# GNSS-receiver.net
KiCad netlist of a schematic drawn in Altium Designer
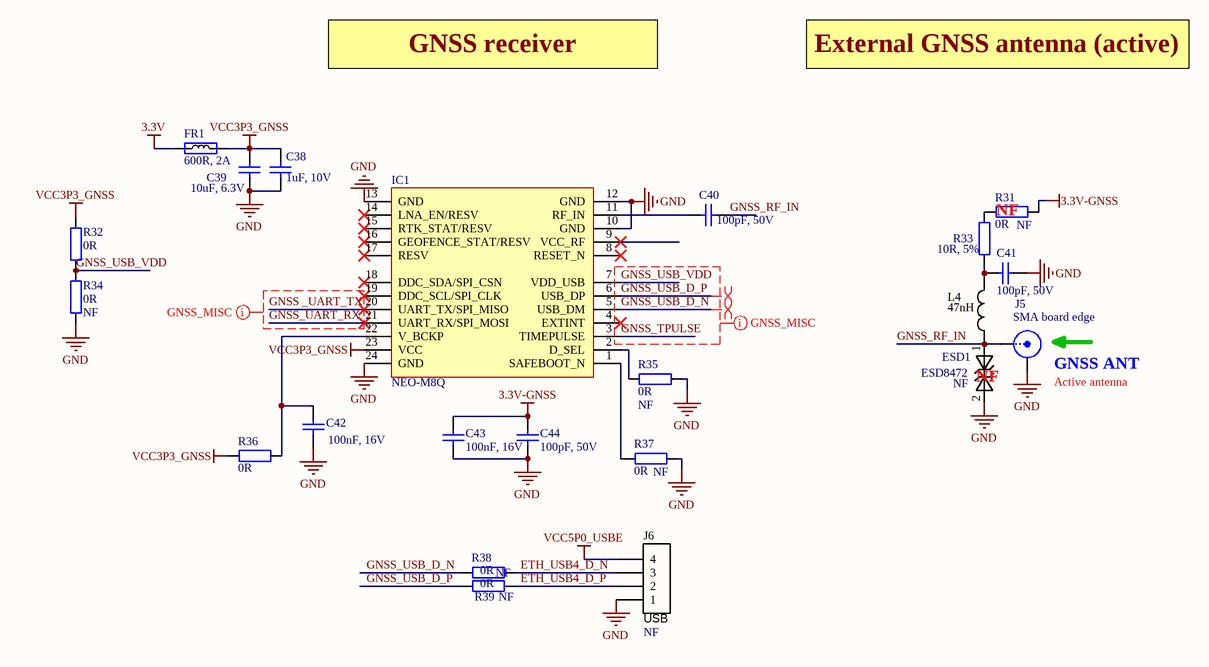
[diagram p0: GNSS-receiver.SchDoc]

(export (version "E")
  (design (tool "Eeschema 10.0.6"))
  (components
    (comp (ref "C38")
      (value "1uF, 10V")
      (footprint "CAP0402")
      (description "CAP CER 1UF 10V X5R 0402")
      (fields (field (name "MANUFACTURER") "Yageo") (field (name "TOLERANCE") "±20%"))
      (libsource (lib "LimeMicroAltiumLib_schLib") (part "Cap_0402"))
    )
    (comp (ref "C39")
      (value "10uF, 6.3V")
      (footprint "CAP0603")
      (fields (field (name "TOLERANCE") "±20%") (field (name "MANUFACTURER") "Yageo"))
      (libsource (lib "LimeFPGAboard_schLib") (part "Cap_0603"))
    )
    (comp (ref "C40")
      (value "100pF, 50V")
      (footprint "CAP0402")
      (fields (field (name "TOLERANCE") "±5%") (field (name "MANUFACTURER") "Yageo"))
      (libsource (lib "LimeMicroAltiumLib_schLib") (part "Cap_0402"))
    )
    (comp (ref "C41")
      (value "100pF, 50V")
      (footprint "CAP0402")
      (fields (field (name "TOLERANCE") "±5%") (field (name "MANUFACTURER") "Yageo"))
      (libsource (lib "LimeMicroAltiumLib_schLib") (part "Cap_0402"))
    )
    (comp (ref "C42")
      (value "100nF, 16V")
      (footprint "CAP0402")
      (fields
        (field (name "TOLERANCE") "10 %")
        (field (name "MANUFACTURER") "Murata Electronics")
        (field (name "MANUFACTURER PART NUMBER") "GRM155R71C104KA88D")
      )
      (libsource (lib "LimeFPGAboard_schLib") (part "Cap_0603"))
    )
    (comp (ref "C43")
      (value "100nF, 16V")
      (footprint "CAP0402")
      (fields
        (field (name "MANUFACTURER") "Murata Electronics")
        (field (name "TOLERANCE") "10 %")
        (field (name "MANUFACTURER PART NUMBER") "GRM155R71C104KA88D")
      )
      (libsource (lib "LimeMicroAltiumLib_schLib") (part "Cap_0402"))
    )
    (comp (ref "C44")
      (value "100pF, 50V")
      (footprint "CAP0402")
      (fields (field (name "TOLERANCE") "±5%") (field (name "MANUFACTURER") "Yageo"))
      (libsource (lib "LimeMicroAltiumLib_schLib") (part "Cap_0402"))
    )
    (comp (ref "ESD1")
      (value "ESD8472")
      (footprint "ESD8472_X3DFN2")
      (fields (field (name "MANUFACTURER") "ON Semiconductor") (field (name "ASSEMBLY INFO") "NF"))
      (libsource (lib "LimeMicroAltiumLib_schLib") (part "ESD8472"))
    )
    (comp (ref "FR1")
      (value "600R, 2A")
      (footprint "RES0805")
      (fields (field (name "MANUFACTURER") "TDK Corporation"))
      (libsource (lib "LimeFPGAboard_schLib") (part "Ferrite"))
    )
    (comp (ref "IC1")
      (value "NEO-M8Q")
      (footprint "NEO-7M/8M")
      (description "GNSS engine for GPS/QZSS, GLONASS")
      (fields (field (name "MANUFACTURER") "u-blox") (field (name "MANUFACTURER PART NUMBER") "NEO-M8Q-0"))
      (libsource (lib "LimeMicroAltiumLib_schLib") (part "NEO-M8P_M8M"))
    )
    (comp (ref "J5")
      (value "SMA board edge")
      (footprint "SMA_connector_board_edge_SM")
      (description "CONN SMA JACK STR 50OHM EDGE MNT")
      (fields (field (name "MANUFACTURER") "RF Solutions"))
      (libsource (lib "LimeMicroAltiumLib_schLib") (part "RF_IF_connector"))
    )
    (comp (ref "J6")
      (value "USB")
      (footprint "HEADER4X1_TH")
      (description "Header, 4-pin")
      (fields (field (name "ASSEMBLY INFO") "NF") (field (name "MANUFACTURER") "Wurth Electronics Inc."))
      (libsource (lib "LimeMicroAltiumLib_schLib") (part "Header4P"))
    )
    (comp (ref "L4")
      (value "47nH")
      (footprint "RES0402")
      (fields
        (field (name "MANUFACTURER") "COILCRAFT")
        (field (name "MANUFACTURER PART NUMBER") "0402HP-47NXJLU")
      )
      (libsource (lib "LimeMicroAltiumLib_schLib") (part "Inductor_0603"))
    )
    (comp (ref "R31")
      (value "0R")
      (footprint "RES0402")
      (fields
        (field (name "ASSEMBLY INFO") "NF")
        (field (name "MANUFACTURER") "Yageo")
        (field (name "TOLERANCE") "Jumper")
      )
      (libsource (lib "LimeMicroAltiumLib_schLib") (part "Res_0402"))
    )
    (comp (ref "R32")
      (value "0R")
      (footprint "RES0402")
      (fields (field (name "MANUFACTURER") "Yageo") (field (name "TOLERANCE") "Jumper"))
      (libsource (lib "LimeMicroAltiumLib_schLib") (part "Res_0402"))
    )
    (comp (ref "R33")
      (value "10R, 5%")
      (footprint "RES0402")
      (fields (field (name "TOLERANCE") "±5%") (field (name "MANUFACTURER") "Yageo"))
      (libsource (lib "LimeMicroAltiumLib_schLib") (part "Res_0402"))
    )
    (comp (ref "R34")
      (value "0R")
      (footprint "RES0402")
      (fields
        (field (name "ASSEMBLY INFO") "NF")
        (field (name "MANUFACTURER") "Yageo")
        (field (name "TOLERANCE") "Jumper")
      )
      (libsource (lib "LimeMicroAltiumLib_schLib") (part "Res_0402"))
    )
    (comp (ref "R35")
      (value "0R")
      (footprint "RES0402")
      (fields
        (field (name "MANUFACTURER") "Yageo")
        (field (name "TOLERANCE") "Jumper")
        (field (name "ASSEMBLY INFO") "NF")
      )
      (libsource (lib "lib-hiony") (part "Res_0402_1"))
    )
    (comp (ref "R36")
      (value "0R")
      (footprint "RES0402")
      (fields (field (name "MANUFACTURER") "Yageo") (field (name "TOLERANCE") "Jumper"))
      (libsource (lib "LimeMicroAltiumLib_schLib") (part "Res_0402"))
    )
    (comp (ref "R37")
      (value "0R")
      (footprint "RES0402")
      (fields
        (field (name "ASSEMBLY INFO") "NF")
        (field (name "MANUFACTURER") "Yageo")
        (field (name "TOLERANCE") "Jumper")
      )
      (libsource (lib "LimeMicroAltiumLib_schLib") (part "Res_0402"))
    )
    (comp (ref "R38")
      (value "0R")
      (footprint "RES0402")
      (fields
        (field (name "MANUFACTURER") "Yageo")
        (field (name "ASSEMBLY INFO") "NF")
        (field (name "TOLERANCE") "Jumper")
      )
      (libsource (lib "LimeFPGAboard_schLib") (part "Res_0402"))
    )
    (comp (ref "R39")
      (value "0R")
      (footprint "RES0402")
      (fields
        (field (name "MANUFACTURER") "Yageo")
        (field (name "ASSEMBLY INFO") "NF")
        (field (name "TOLERANCE") "Jumper")
      )
      (libsource (lib "LimeFPGAboard_schLib") (part "Res_0402"))
    )
  )
  (nets
    (net (code "1") (name "/ETH_USB4_D_N") (class "Default")
      (node (ref "J6") (pin "3") (pinfunction "3_3") (pintype "passive"))
      (node (ref "R38") (pin "1") (pinfunction "1_1") (pintype "passive"))
    )
    (net (code "2") (name "/ETH_USB4_D_P") (class "Default")
      (node (ref "J6") (pin "2") (pinfunction "2_2") (pintype "passive"))
      (node (ref "R39") (pin "1") (pinfunction "1_1") (pintype "passive"))
    )
    (net (code "3") (name "/GNSS _UART_TX") (class "Default")
      (node (ref "IC1") (pin "20") (pinfunction "UART_TX/SPI_MISO_20") (pintype "passive+no_connect"))
    )
    (net (code "4") (name "/GNSS_RF_IN") (class "Default")
      (node (ref "C40") (pin "1") (pinfunction "1_1") (pintype "passive"))
      (node (ref "ESD1") (pin "1") (pinfunction "1_1") (pintype "passive"))
      (node (ref "J5") (pin "1") (pinfunction "X_1") (pintype "passive"))
      (node (ref "L4") (pin "1") (pinfunction "1_1") (pintype "passive"))
    )
    (net (code "5") (name "/GNSS_TPULSE") (class "Default")
      (node (ref "IC1") (pin "3") (pinfunction "TIMEPULSE_3") (pintype "passive"))
    )
    (net (code "6") (name "/GNSS_UART_RX") (class "Default")
      (node (ref "IC1") (pin "21") (pinfunction "UART_RX/SPI_MOSI_21") (pintype "passive+no_connect"))
    )
    (net (code "7") (name "/GNSS_USB_D_N") (class "Default")
      (node (ref "IC1") (pin "5") (pinfunction "USB_DM_5") (pintype "passive"))
      (node (ref "R38") (pin "2") (pinfunction "2_2") (pintype "passive"))
    )
    (net (code "8") (name "/GNSS_USB_D_P") (class "Default")
      (node (ref "IC1") (pin "6") (pinfunction "USB_DP_6") (pintype "passive"))
      (node (ref "R39") (pin "2") (pinfunction "2_2") (pintype "passive"))
    )
    (net (code "9") (name "/GNSS_USB_VDD") (class "Default")
      (node (ref "IC1") (pin "7") (pinfunction "VDD_USB_7") (pintype "passive"))
      (node (ref "R32") (pin "1") (pinfunction "1_1") (pintype "passive"))
      (node (ref "R34") (pin "1") (pinfunction "1_1") (pintype "passive"))
    )
    (net (code "10") (name "3.3V") (class "Default")
      (node (ref "FR1") (pin "1") (pinfunction "1_1") (pintype "passive"))
    )
    (net (code "11") (name "3.3V-GNSS") (class "Default")
      (node (ref "C43") (pin "2") (pinfunction "2_2") (pintype "passive"))
      (node (ref "C44") (pin "1") (pinfunction "1_1") (pintype "passive"))
      (node (ref "R31") (pin "1") (pinfunction "1_1") (pintype "passive"))
    )
    (net (code "12") (name "GND") (class "Default")
      (node (ref "C38") (pin "1") (pinfunction "1_1") (pintype "passive"))
      (node (ref "C39") (pin "1") (pinfunction "1_1") (pintype "passive"))
      (node (ref "C41") (pin "2") (pinfunction "2_2") (pintype "passive"))
      (node (ref "C42") (pin "2") (pinfunction "2_2") (pintype "passive"))
      (node (ref "C43") (pin "1") (pinfunction "1_1") (pintype "passive"))
      (node (ref "C44") (pin "2") (pinfunction "2_2") (pintype "passive"))
      (node (ref "ESD1") (pin "2") (pinfunction "2_2") (pintype "passive"))
      (node (ref "IC1") (pin "10") (pinfunction "GND_10") (pintype "passive"))
      (node (ref "IC1") (pin "12") (pinfunction "GND_12") (pintype "passive"))
      (node (ref "IC1") (pin "13") (pinfunction "GND_13") (pintype "passive"))
      (node (ref "IC1") (pin "24") (pinfunction "GND_24") (pintype "passive"))
      (node (ref "J5") (pin "2") (pinfunction "Y_2") (pintype "passive"))
      (node (ref "J6") (pin "1") (pinfunction "1_1") (pintype "passive"))
      (node (ref "R34") (pin "2") (pinfunction "2_2") (pintype "passive"))
      (node (ref "R35") (pin "2") (pinfunction "2_2") (pintype "passive"))
      (node (ref "R37") (pin "1") (pinfunction "1_1") (pintype "passive"))
    )
    (net (code "13") (name "Net-(C41-Pad1)") (class "Default")
      (node (ref "C41") (pin "1") (pinfunction "1_1") (pintype "passive"))
      (node (ref "L4") (pin "2") (pinfunction "2_2") (pintype "passive"))
      (node (ref "R33") (pin "2") (pinfunction "2_2") (pintype "passive"))
    )
    (net (code "14") (name "Net-(IC1-D_SEL)") (class "Default")
      (node (ref "IC1") (pin "2") (pinfunction "D_SEL_2") (pintype "passive"))
      (node (ref "R35") (pin "1") (pinfunction "1_1") (pintype "passive"))
    )
    (net (code "15") (name "Net-(IC1-RF_IN)") (class "Default")
      (node (ref "C40") (pin "2") (pinfunction "2_2") (pintype "passive"))
      (node (ref "IC1") (pin "11") (pinfunction "RF_IN_11") (pintype "passive"))
    )
    (net (code "16") (name "Net-(IC1-SAFEBOOT_N)") (class "Default")
      (node (ref "IC1") (pin "1") (pinfunction "SAFEBOOT_N_1") (pintype "passive"))
      (node (ref "R37") (pin "2") (pinfunction "2_2") (pintype "passive"))
    )
    (net (code "17") (name "Net-(IC1-V_BCKP)") (class "Default")
      (node (ref "C42") (pin "1") (pinfunction "1_1") (pintype "passive"))
      (node (ref "IC1") (pin "22") (pinfunction "V_BCKP_22") (pintype "passive"))
      (node (ref "R36") (pin "1") (pinfunction "1_1") (pintype "passive"))
    )
    (net (code "18") (name "Net-(R31-Pad2)") (class "Default")
      (node (ref "R31") (pin "2") (pinfunction "2_2") (pintype "passive"))
      (node (ref "R33") (pin "1") (pinfunction "1_1") (pintype "passive"))
    )
    (net (code "19") (name "VCC3P3_GNSS") (class "Default")
      (node (ref "C38") (pin "2") (pinfunction "2_2") (pintype "passive"))
      (node (ref "C39") (pin "2") (pinfunction "2_2") (pintype "passive"))
      (node (ref "FR1") (pin "2") (pinfunction "2_2") (pintype "passive"))
      (node (ref "IC1") (pin "23") (pinfunction "VCC_23") (pintype "passive"))
      (node (ref "R32") (pin "2") (pinfunction "2_2") (pintype "passive"))
      (node (ref "R36") (pin "2") (pinfunction "2_2") (pintype "passive"))
    )
    (net (code "20") (name "VCC5P0_USBE") (class "Default")
      (node (ref "J6") (pin "4") (pinfunction "4_4") (pintype "passive"))
    )
    (net (code "21") (name "unconnected-(IC1-DDC_SCL{slash}SPI_CLK-Pad19)") (class "Default")
      (node (ref "IC1") (pin "19") (pinfunction "DDC_SCL/SPI_CLK_19") (pintype "passive+no_connect"))
    )
    (net (code "22") (name "unconnected-(IC1-DDC_SDA{slash}SPI_CSN-Pad18)") (class "Default")
      (node (ref "IC1") (pin "18") (pinfunction "DDC_SDA/SPI_CSN_18") (pintype "passive+no_connect"))
    )
    (net (code "23") (name "unconnected-(IC1-EXTINT-Pad4)") (class "Default")
      (node (ref "IC1") (pin "4") (pinfunction "EXTINT_4") (pintype "passive+no_connect"))
    )
    (net (code "24") (name "unconnected-(IC1-GEOFENCE_STAT{slash}RESV-Pad16)") (class "Default")
      (node (ref "IC1") (pin "16") (pinfunction "GEOFENCE_STAT/RESV_16") (pintype "passive+no_connect"))
    )
    (net (code "25") (name "unconnected-(IC1-LNA_EN{slash}RESV-Pad14)") (class "Default")
      (node (ref "IC1") (pin "14") (pinfunction "LNA_EN/RESV_14") (pintype "passive+no_connect"))
    )
    (net (code "26") (name "unconnected-(IC1-RESET_N-Pad8)") (class "Default")
      (node (ref "IC1") (pin "8") (pinfunction "RESET_N_8") (pintype "passive+no_connect"))
    )
    (net (code "27") (name "unconnected-(IC1-RESV-Pad17)") (class "Default")
      (node (ref "IC1") (pin "17") (pinfunction "RESV_17") (pintype "passive+no_connect"))
    )
    (net (code "28") (name "unconnected-(IC1-RTK_STAT{slash}RESV-Pad15)") (class "Default")
      (node (ref "IC1") (pin "15") (pinfunction "RTK_STAT/RESV_15") (pintype "passive+no_connect"))
    )
    (net (code "29") (name "unconnected-(IC1-VCC_RF-Pad9)") (class "Default")
      (node (ref "IC1") (pin "9") (pinfunction "VCC_RF_9") (pintype "passive+no_connect"))
    )
  )
)
